# heater.net
KiCad netlist of a schematic drawn in EAGLE
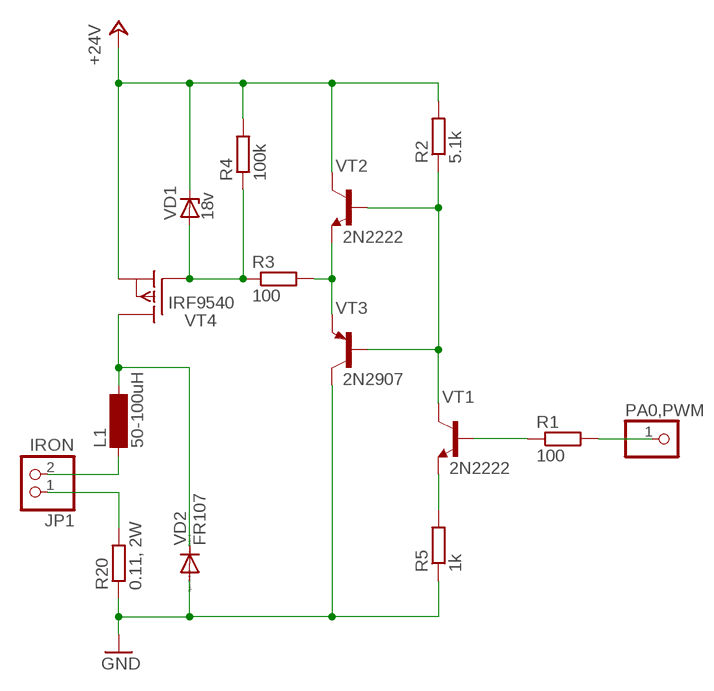
[diagram p0: schematic, sheet 1]

(export (version "E")
  (design (tool "Eeschema 10.0.6"))
  (components
    (comp (ref "JP1")
      (value "IRON")
      (footprint "eagle-import:1X02")
      (libsource (lib "eagle-import") (part "PINHD-1X2"))
    )
    (comp (ref "L1")
      (value "50-100uH")
      (footprint "eagle-import:SD8")
      (libsource (lib "eagle-import") (part "SD8"))
    )
    (comp (ref "PA0,PWM")
      (value "PINHD-1X1")
      (footprint "eagle-import:1X01")
      (libsource (lib "eagle-import") (part "PINHD-1X1"))
    )
    (comp (ref "R1")
      (value "100")
      (footprint "eagle-import:0207_10")
      (libsource (lib "eagle-import") (part "R-EU_0207/10"))
    )
    (comp (ref "R2")
      (value "5.1k")
      (footprint "eagle-import:0207_10")
      (libsource (lib "eagle-import") (part "R-EU_0207/10"))
    )
    (comp (ref "R3")
      (value "100")
      (footprint "eagle-import:0207_10")
      (libsource (lib "eagle-import") (part "R-EU_0207/10"))
    )
    (comp (ref "R4")
      (value "100k")
      (footprint "eagle-import:0207_10")
      (libsource (lib "eagle-import") (part "R-EU_0207/10"))
    )
    (comp (ref "R5")
      (value "1k")
      (footprint "eagle-import:0207_10")
      (libsource (lib "eagle-import") (part "R-EU_0207/10"))
    )
    (comp (ref "R20")
      (value "0.11, 2W")
      (footprint "eagle-import:0207_10")
      (libsource (lib "eagle-import") (part "R-EU_0207/10"))
    )
    (comp (ref "VD1")
      (value "18v")
      (footprint "eagle-import:C1702-15")
      (libsource (lib "eagle-import") (part "ZENER-DIODEC1702-15"))
    )
    (comp (ref "VD2")
      (value "FR107")
      (footprint "eagle-import:DO41-10")
      (libsource (lib "eagle-import") (part "1N4004"))
    )
    (comp (ref "VT1")
      (value "2N2222")
      (footprint "eagle-import:TO18")
      (libsource (lib "eagle-import") (part "2N2222"))
    )
    (comp (ref "VT2")
      (value "2N2222")
      (footprint "eagle-import:TO18")
      (libsource (lib "eagle-import") (part "2N2222"))
    )
    (comp (ref "VT3")
      (value "2N2907")
      (footprint "eagle-import:TO18")
      (libsource (lib "eagle-import") (part "-PNP-TO18-EBC2N2907"))
    )
    (comp (ref "VT4")
      (value "IRF9540")
      (footprint "eagle-import:TO220")
      (libsource (lib "eagle-import") (part "IRF9530"))
    )
  )
  (nets
    (net (code "1") (name "+24V") (class "Default")
      (node (ref "R2") (pin "2") (pinfunction "2_2") (pintype "passive"))
      (node (ref "R4") (pin "2") (pinfunction "2_2") (pintype "passive"))
      (node (ref "VD1") (pin "C") (pinfunction "C_C") (pintype "passive"))
      (node (ref "VT2") (pin "3") (pinfunction "C_3") (pintype "passive"))
      (node (ref "VT4") (pin "3") (pinfunction "S_3") (pintype "passive"))
    )
    (net (code "2") (name "GND") (class "Default")
      (node (ref "R20") (pin "1") (pinfunction "1_1") (pintype "passive"))
      (node (ref "R5") (pin "1") (pinfunction "1_1") (pintype "passive"))
      (node (ref "VD2") (pin "A") (pinfunction "A_A") (pintype "passive"))
      (node (ref "VT3") (pin "3") (pinfunction "C_3") (pintype "passive"))
    )
    (net (code "3") (name "Net-(JP1-Pad1)") (class "Default")
      (node (ref "JP1") (pin "1") (pinfunction "1_1") (pintype "passive"))
      (node (ref "R20") (pin "2") (pinfunction "2_2") (pintype "passive"))
    )
    (net (code "4") (name "Net-(JP1-Pad2)") (class "Default")
      (node (ref "JP1") (pin "2") (pinfunction "2_2") (pintype "passive"))
      (node (ref "L1") (pin "1") (pinfunction "1_1") (pintype "passive"))
    )
    (net (code "5") (name "Net-(PA0,PWM-Pad1)") (class "Default")
      (node (ref "PA0,PWM") (pin "1") (pinfunction "1_1") (pintype "passive"))
      (node (ref "R1") (pin "2") (pinfunction "2_2") (pintype "passive"))
    )
    (net (code "6") (name "Net-(VT1-B)") (class "Default")
      (node (ref "R1") (pin "1") (pinfunction "1_1") (pintype "passive"))
      (node (ref "VT1") (pin "2") (pinfunction "B_2") (pintype "passive"))
    )
    (net (code "7") (name "Net-(VT1-C)") (class "Default")
      (node (ref "R2") (pin "1") (pinfunction "1_1") (pintype "passive"))
      (node (ref "VT1") (pin "3") (pinfunction "C_3") (pintype "passive"))
      (node (ref "VT2") (pin "2") (pinfunction "B_2") (pintype "passive"))
      (node (ref "VT3") (pin "2") (pinfunction "B_2") (pintype "passive"))
    )
    (net (code "8") (name "Net-(VT1-E)") (class "Default")
      (node (ref "R5") (pin "2") (pinfunction "2_2") (pintype "passive"))
      (node (ref "VT1") (pin "1") (pinfunction "E_1") (pintype "passive"))
    )
    (net (code "9") (name "Net-(VT2-E)") (class "Default")
      (node (ref "R3") (pin "2") (pinfunction "2_2") (pintype "passive"))
      (node (ref "VT2") (pin "1") (pinfunction "E_1") (pintype "passive"))
      (node (ref "VT3") (pin "1") (pinfunction "E_1") (pintype "passive"))
    )
    (net (code "10") (name "Net-(VT4-D)") (class "Default")
      (node (ref "L1") (pin "2") (pinfunction "2_2") (pintype "passive"))
      (node (ref "VD2") (pin "C") (pinfunction "C_C") (pintype "passive"))
      (node (ref "VT4") (pin "2") (pinfunction "D_2") (pintype "passive"))
    )
    (net (code "11") (name "Net-(VT4-G)") (class "Default")
      (node (ref "R3") (pin "1") (pinfunction "1_1") (pintype "passive"))
      (node (ref "R4") (pin "1") (pinfunction "1_1") (pintype "passive"))
      (node (ref "VD1") (pin "A") (pinfunction "A_A") (pintype "passive"))
      (node (ref "VT4") (pin "1") (pinfunction "G_1") (pintype "passive"))
    )
  )
)
